# PWR.net
KiCad netlist of a schematic drawn in Altium Designer
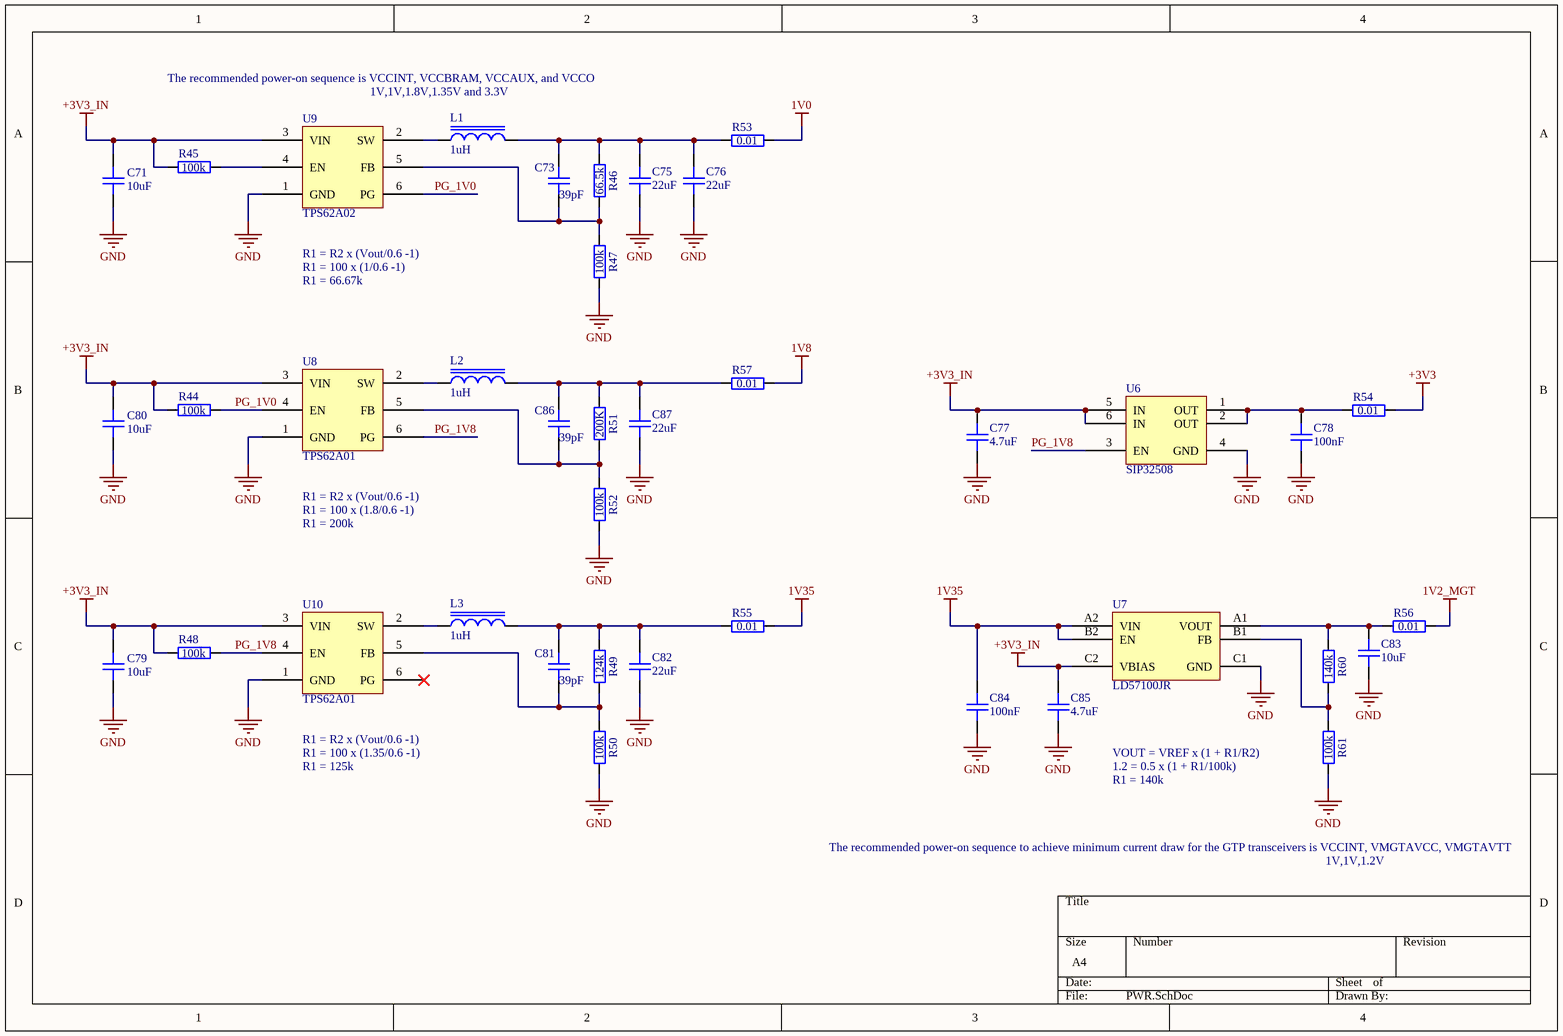
[diagram p0: PWR.SchDoc]

(export (version "E")
  (design (tool "Eeschema 10.0.6"))
  (components
    (comp (ref "C71")
      (value "10uF")
      (footprint "GEN_C_0603")
      (libsource (lib "DSO") (part "CAP 10uF 10V X5R 0603"))
    )
    (comp (ref "C73")
      (value "39pF")
      (footprint "GEN_C_0402")
      (libsource (lib "DSO") (part "CAP 39pF 50V C0G 0402"))
    )
    (comp (ref "C75")
      (value "22uF")
      (footprint "GEN_C_0805")
      (libsource (lib "DSO") (part "CAP 22uF 25V X5R 0805"))
    )
    (comp (ref "C76")
      (value "22uF")
      (footprint "GEN_C_0805")
      (libsource (lib "DSO") (part "CAP 22uF 25V X5R 0805"))
    )
    (comp (ref "C77")
      (value "4.7uF")
      (footprint "GEN_C_0402")
      (libsource (lib "DSO") (part "CAP 4.7uF 6.3V X5R 0402"))
    )
    (comp (ref "C78")
      (value "100nF")
      (footprint "GEN_C_0402")
      (libsource (lib "DSO") (part "CAP 100nF 16V X7R 0402"))
    )
    (comp (ref "C79")
      (value "10uF")
      (footprint "GEN_C_0603")
      (libsource (lib "DSO") (part "CAP 10uF 10V X5R 0603"))
    )
    (comp (ref "C80")
      (value "10uF")
      (footprint "GEN_C_0603")
      (libsource (lib "DSO") (part "CAP 10uF 10V X5R 0603"))
    )
    (comp (ref "C81")
      (value "39pF")
      (footprint "GEN_C_0402")
      (libsource (lib "DSO") (part "CAP 39pF 50V C0G 0402"))
    )
    (comp (ref "C82")
      (value "22uF")
      (footprint "GEN_C_0805")
      (libsource (lib "DSO") (part "CAP 22uF 25V X5R 0805"))
    )
    (comp (ref "C83")
      (value "10uF")
      (footprint "GEN_C_0603")
      (libsource (lib "DSO") (part "CAP 10uF 10V X5R 0603"))
    )
    (comp (ref "C84")
      (value "100nF")
      (footprint "GEN_C_0402")
      (libsource (lib "DSO") (part "CAP 100nF 16V X7R 0402"))
    )
    (comp (ref "C85")
      (value "4.7uF")
      (footprint "GEN_C_0402")
      (libsource (lib "DSO") (part "CAP 4.7uF 6.3V X5R 0402"))
    )
    (comp (ref "C86")
      (value "39pF")
      (footprint "GEN_C_0402")
      (libsource (lib "DSO") (part "CAP 39pF 50V C0G 0402"))
    )
    (comp (ref "C87")
      (value "22uF")
      (footprint "GEN_C_0805")
      (libsource (lib "DSO") (part "CAP 22uF 25V X5R 0805"))
    )
    (comp (ref "L1")
      (value "1uH")
      (footprint "GEN_L_1210")
      (libsource (lib "DSO") (part "IND 1uH 5.5A 32 MOHM 1210"))
    )
    (comp (ref "L2")
      (value "1uH")
      (footprint "GEN_L_1210")
      (libsource (lib "DSO") (part "IND 1uH 5.5A 32 MOHM 1210"))
    )
    (comp (ref "L3")
      (value "1uH")
      (footprint "GEN_L_1210")
      (libsource (lib "DSO") (part "IND 1uH 5.5A 32 MOHM 1210"))
    )
    (comp (ref "R44")
      (value "100k")
      (footprint "GEN_R_0402")
      (fields (field (name "TOLERANCE") "1%"))
      (libsource (lib "") (part "RES 100K OHM 1% 1/10W 0402_1"))
    )
    (comp (ref "R45")
      (value "100k")
      (footprint "GEN_R_0402")
      (fields (field (name "TOLERANCE") "1%"))
      (libsource (lib "") (part "RES 100K OHM 1% 1/10W 0402_1"))
    )
    (comp (ref "R46")
      (value "66.5k")
      (footprint "GEN_R_0402")
      (fields (field (name "TOLERANCE") "1%"))
      (libsource (lib "DSO") (part "RES 66.5K OHM 1% 1/16W 0402"))
    )
    (comp (ref "R47")
      (value "100k")
      (footprint "GEN_R_0402")
      (fields (field (name "TOLERANCE") "1%"))
      (libsource (lib "DSO") (part "RES 100K OHM 1% 1/10W 0402"))
    )
    (comp (ref "R48")
      (value "100k")
      (footprint "GEN_R_0402")
      (fields (field (name "TOLERANCE") "1%"))
      (libsource (lib "") (part "RES 100K OHM 1% 1/10W 0402_1"))
    )
    (comp (ref "R49")
      (value "124k")
      (footprint "GEN_R_0402")
      (fields (field (name "TOLERANCE") "1%"))
      (libsource (lib "DSO") (part "RES 124K OHM 1% 1/10W 0402"))
    )
    (comp (ref "R50")
      (value "100k")
      (footprint "GEN_R_0402")
      (fields (field (name "TOLERANCE") "1%"))
      (libsource (lib "DSO") (part "RES 100K OHM 1% 1/10W 0402"))
    )
    (comp (ref "R51")
      (value "200K")
      (footprint "GEN_R_0402")
      (fields (field (name "TOLERANCE") "1%"))
      (libsource (lib "DSO") (part "RES 200K OHM 1% 1/16W 0402"))
    )
    (comp (ref "R52")
      (value "100k")
      (footprint "GEN_R_0402")
      (fields (field (name "TOLERANCE") "1%"))
      (libsource (lib "DSO") (part "RES 100K OHM 1% 1/10W 0402"))
    )
    (comp (ref "R53")
      (value "0.01")
      (footprint "GEN_R_0603")
      (fields (field (name "TOLERANCE") "1%"))
      (libsource (lib "DSO") (part "RES 0.01 OHM 1% 1/4W 0603"))
    )
    (comp (ref "R54")
      (value "0.01")
      (footprint "GEN_R_0603")
      (fields (field (name "TOLERANCE") "1%"))
      (libsource (lib "DSO") (part "RES 0.01 OHM 1% 1/4W 0603"))
    )
    (comp (ref "R55")
      (value "0.01")
      (footprint "GEN_R_0603")
      (fields (field (name "TOLERANCE") "1%"))
      (libsource (lib "DSO") (part "RES 0.01 OHM 1% 1/4W 0603"))
    )
    (comp (ref "R56")
      (value "0.01")
      (footprint "GEN_R_0603")
      (fields (field (name "TOLERANCE") "1%"))
      (libsource (lib "DSO") (part "RES 0.01 OHM 1% 1/4W 0603"))
    )
    (comp (ref "R57")
      (value "0.01")
      (footprint "GEN_R_0603")
      (fields (field (name "TOLERANCE") "1%"))
      (libsource (lib "DSO") (part "RES 0.01 OHM 1% 1/4W 0603"))
    )
    (comp (ref "R60")
      (value "140k")
      (footprint "GEN_R_0402")
      (fields (field (name "TOLERANCE") "1%"))
      (libsource (lib "DSO") (part "RES 140K OHM 1% 1/10W 0402"))
    )
    (comp (ref "R61")
      (value "100k")
      (footprint "GEN_R_0402")
      (fields (field (name "TOLERANCE") "1%"))
      (libsource (lib "DSO") (part "RES 100K OHM 1% 1/10W 0402"))
    )
    (comp (ref "U6")
      (value "SIP32508")
      (footprint "VISH_TSOT6")
      (libsource (lib "DSO") (part "IC SWITCH LOAD SIP32508"))
    )
    (comp (ref "U7")
      (value "LD57100JR")
      (footprint "ST_FlipChip6")
      (libsource (lib "DSO") (part "IC LDO LD57100JR"))
    )
    (comp (ref "U8")
      (value "TPS62A01")
      (footprint "TI_SOT563_DRL0006A")
      (libsource (lib "DSO") (part "IC BUCK TPS62A01"))
    )
    (comp (ref "U9")
      (value "TPS62A02")
      (footprint "TI_SOT563_DRL0006A")
      (libsource (lib "DSO") (part "IC BUCK TPS62A02"))
    )
    (comp (ref "U10")
      (value "TPS62A01")
      (footprint "TI_SOT563_DRL0006A")
      (libsource (lib "DSO") (part "IC BUCK TPS62A01"))
    )
  )
  (nets
    (net (code "1") (name "+3V3") (class "Default")
      (node (ref "R54") (pin "2") (pinfunction "2_2") (pintype "passive"))
    )
    (net (code "2") (name "+3V3_IN") (class "Default")
      (node (ref "C71") (pin "2") (pinfunction "2_2") (pintype "passive"))
      (node (ref "C77") (pin "2") (pinfunction "2_2") (pintype "passive"))
      (node (ref "C79") (pin "2") (pinfunction "2_2") (pintype "passive"))
      (node (ref "C80") (pin "2") (pinfunction "2_2") (pintype "passive"))
      (node (ref "C85") (pin "2") (pinfunction "2_2") (pintype "passive"))
      (node (ref "R44") (pin "2") (pinfunction "2_2") (pintype "passive"))
      (node (ref "R45") (pin "2") (pinfunction "2_2") (pintype "passive"))
      (node (ref "R48") (pin "2") (pinfunction "2_2") (pintype "passive"))
      (node (ref "U10") (pin "3") (pinfunction "VIN_3") (pintype "power_in"))
      (node (ref "U6") (pin "5") (pinfunction "IN_5") (pintype "passive"))
      (node (ref "U6") (pin "6") (pinfunction "IN_6") (pintype "passive"))
      (node (ref "U7") (pin "C2") (pinfunction "VBIAS_C2") (pintype "passive"))
      (node (ref "U8") (pin "3") (pinfunction "VIN_3") (pintype "power_in"))
      (node (ref "U9") (pin "3") (pinfunction "VIN_3") (pintype "power_in"))
    )
    (net (code "3") (name "/PG_1V0") (class "Default")
      (node (ref "R44") (pin "1") (pinfunction "1_1") (pintype "passive"))
      (node (ref "U8") (pin "4") (pinfunction "EN_4") (pintype "passive"))
      (node (ref "U9") (pin "6") (pinfunction "PG_6") (pintype "passive"))
    )
    (net (code "4") (name "/PG_1V8") (class "Default")
      (node (ref "R48") (pin "1") (pinfunction "1_1") (pintype "passive"))
      (node (ref "U10") (pin "4") (pinfunction "EN_4") (pintype "passive"))
      (node (ref "U6") (pin "3") (pinfunction "EN_3") (pintype "passive"))
      (node (ref "U8") (pin "6") (pinfunction "PG_6") (pintype "passive"))
    )
    (net (code "5") (name "1V0") (class "Default")
      (node (ref "R53") (pin "2") (pinfunction "2_2") (pintype "passive"))
    )
    (net (code "6") (name "1V2_MGT") (class "Default")
      (node (ref "R56") (pin "2") (pinfunction "2_2") (pintype "passive"))
    )
    (net (code "7") (name "1V8") (class "Default")
      (node (ref "R57") (pin "2") (pinfunction "2_2") (pintype "passive"))
    )
    (net (code "8") (name "1V35") (class "Default")
      (node (ref "C84") (pin "2") (pinfunction "2_2") (pintype "passive"))
      (node (ref "R55") (pin "2") (pinfunction "2_2") (pintype "passive"))
      (node (ref "U7") (pin "A2") (pinfunction "VIN_A2") (pintype "passive"))
      (node (ref "U7") (pin "B2") (pinfunction "EN_B2") (pintype "passive"))
    )
    (net (code "9") (name "GND") (class "Default")
      (node (ref "C71") (pin "1") (pinfunction "1_1") (pintype "passive"))
      (node (ref "C75") (pin "1") (pinfunction "1_1") (pintype "passive"))
      (node (ref "C76") (pin "1") (pinfunction "1_1") (pintype "passive"))
      (node (ref "C77") (pin "1") (pinfunction "1_1") (pintype "passive"))
      (node (ref "C78") (pin "1") (pinfunction "1_1") (pintype "passive"))
      (node (ref "C79") (pin "1") (pinfunction "1_1") (pintype "passive"))
      (node (ref "C80") (pin "1") (pinfunction "1_1") (pintype "passive"))
      (node (ref "C82") (pin "1") (pinfunction "1_1") (pintype "passive"))
      (node (ref "C83") (pin "1") (pinfunction "1_1") (pintype "passive"))
      (node (ref "C84") (pin "1") (pinfunction "1_1") (pintype "passive"))
      (node (ref "C85") (pin "1") (pinfunction "1_1") (pintype "passive"))
      (node (ref "C87") (pin "1") (pinfunction "1_1") (pintype "passive"))
      (node (ref "R47") (pin "1") (pinfunction "1_1") (pintype "passive"))
      (node (ref "R50") (pin "1") (pinfunction "1_1") (pintype "passive"))
      (node (ref "R52") (pin "1") (pinfunction "1_1") (pintype "passive"))
      (node (ref "R61") (pin "1") (pinfunction "1_1") (pintype "passive"))
      (node (ref "U10") (pin "1") (pinfunction "GND_1") (pintype "power_in"))
      (node (ref "U6") (pin "4") (pinfunction "GND_4") (pintype "passive"))
      (node (ref "U7") (pin "C1") (pinfunction "GND_C1") (pintype "passive"))
      (node (ref "U8") (pin "1") (pinfunction "GND_1") (pintype "power_in"))
      (node (ref "U9") (pin "1") (pinfunction "GND_1") (pintype "power_in"))
    )
    (net (code "10") (name "Net-(C73-Pad2)") (class "Default")
      (node (ref "C73") (pin "2") (pinfunction "2_2") (pintype "passive"))
      (node (ref "C75") (pin "2") (pinfunction "2_2") (pintype "passive"))
      (node (ref "C76") (pin "2") (pinfunction "2_2") (pintype "passive"))
      (node (ref "L1") (pin "2") (pinfunction "2_2") (pintype "passive"))
      (node (ref "R46") (pin "2") (pinfunction "2_2") (pintype "passive"))
      (node (ref "R53") (pin "1") (pinfunction "1_1") (pintype "passive"))
    )
    (net (code "11") (name "Net-(C78-Pad2)") (class "Default")
      (node (ref "C78") (pin "2") (pinfunction "2_2") (pintype "passive"))
      (node (ref "R54") (pin "1") (pinfunction "1_1") (pintype "passive"))
      (node (ref "U6") (pin "1") (pinfunction "OUT_1") (pintype "passive"))
      (node (ref "U6") (pin "2") (pinfunction "OUT_2") (pintype "passive"))
    )
    (net (code "12") (name "Net-(C81-Pad2)") (class "Default")
      (node (ref "C81") (pin "2") (pinfunction "2_2") (pintype "passive"))
      (node (ref "C82") (pin "2") (pinfunction "2_2") (pintype "passive"))
      (node (ref "L3") (pin "2") (pinfunction "2_2") (pintype "passive"))
      (node (ref "R49") (pin "2") (pinfunction "2_2") (pintype "passive"))
      (node (ref "R55") (pin "1") (pinfunction "1_1") (pintype "passive"))
    )
    (net (code "13") (name "Net-(C86-Pad2)") (class "Default")
      (node (ref "C86") (pin "2") (pinfunction "2_2") (pintype "passive"))
      (node (ref "C87") (pin "2") (pinfunction "2_2") (pintype "passive"))
      (node (ref "L2") (pin "2") (pinfunction "2_2") (pintype "passive"))
      (node (ref "R51") (pin "2") (pinfunction "2_2") (pintype "passive"))
      (node (ref "R57") (pin "1") (pinfunction "1_1") (pintype "passive"))
    )
    (net (code "14") (name "Net-(U7-FB)") (class "Default")
      (node (ref "R60") (pin "1") (pinfunction "1_1") (pintype "passive"))
      (node (ref "R61") (pin "2") (pinfunction "2_2") (pintype "passive"))
      (node (ref "U7") (pin "B1") (pinfunction "FB_B1") (pintype "passive"))
    )
    (net (code "15") (name "Net-(U7-VOUT)") (class "Default")
      (node (ref "C83") (pin "2") (pinfunction "2_2") (pintype "passive"))
      (node (ref "R56") (pin "1") (pinfunction "1_1") (pintype "passive"))
      (node (ref "R60") (pin "2") (pinfunction "2_2") (pintype "passive"))
      (node (ref "U7") (pin "A1") (pinfunction "VOUT_A1") (pintype "passive"))
    )
    (net (code "16") (name "Net-(U8-FB)") (class "Default")
      (node (ref "C86") (pin "1") (pinfunction "1_1") (pintype "passive"))
      (node (ref "R51") (pin "1") (pinfunction "1_1") (pintype "passive"))
      (node (ref "R52") (pin "2") (pinfunction "2_2") (pintype "passive"))
      (node (ref "U8") (pin "5") (pinfunction "FB_5") (pintype "passive"))
    )
    (net (code "17") (name "Net-(U8-SW)") (class "Default")
      (node (ref "L2") (pin "1") (pinfunction "1_1") (pintype "passive"))
      (node (ref "U8") (pin "2") (pinfunction "SW_2") (pintype "passive"))
    )
    (net (code "18") (name "Net-(U9-EN)") (class "Default")
      (node (ref "R45") (pin "1") (pinfunction "1_1") (pintype "passive"))
      (node (ref "U9") (pin "4") (pinfunction "EN_4") (pintype "passive"))
    )
    (net (code "19") (name "Net-(U9-FB)") (class "Default")
      (node (ref "C73") (pin "1") (pinfunction "1_1") (pintype "passive"))
      (node (ref "R46") (pin "1") (pinfunction "1_1") (pintype "passive"))
      (node (ref "R47") (pin "2") (pinfunction "2_2") (pintype "passive"))
      (node (ref "U9") (pin "5") (pinfunction "FB_5") (pintype "passive"))
    )
    (net (code "20") (name "Net-(U9-SW)") (class "Default")
      (node (ref "L1") (pin "1") (pinfunction "1_1") (pintype "passive"))
      (node (ref "U9") (pin "2") (pinfunction "SW_2") (pintype "passive"))
    )
    (net (code "21") (name "Net-(U10-FB)") (class "Default")
      (node (ref "C81") (pin "1") (pinfunction "1_1") (pintype "passive"))
      (node (ref "R49") (pin "1") (pinfunction "1_1") (pintype "passive"))
      (node (ref "R50") (pin "2") (pinfunction "2_2") (pintype "passive"))
      (node (ref "U10") (pin "5") (pinfunction "FB_5") (pintype "passive"))
    )
    (net (code "22") (name "Net-(U10-SW)") (class "Default")
      (node (ref "L3") (pin "1") (pinfunction "1_1") (pintype "passive"))
      (node (ref "U10") (pin "2") (pinfunction "SW_2") (pintype "passive"))
    )
    (net (code "23") (name "unconnected-(U10-PG-Pad6)") (class "Default")
      (node (ref "U10") (pin "6") (pinfunction "PG_6") (pintype "passive+no_connect"))
    )
  )
)
